# SoftCore_SA_P3.net
KiCad netlist of a schematic drawn in Altium Designer
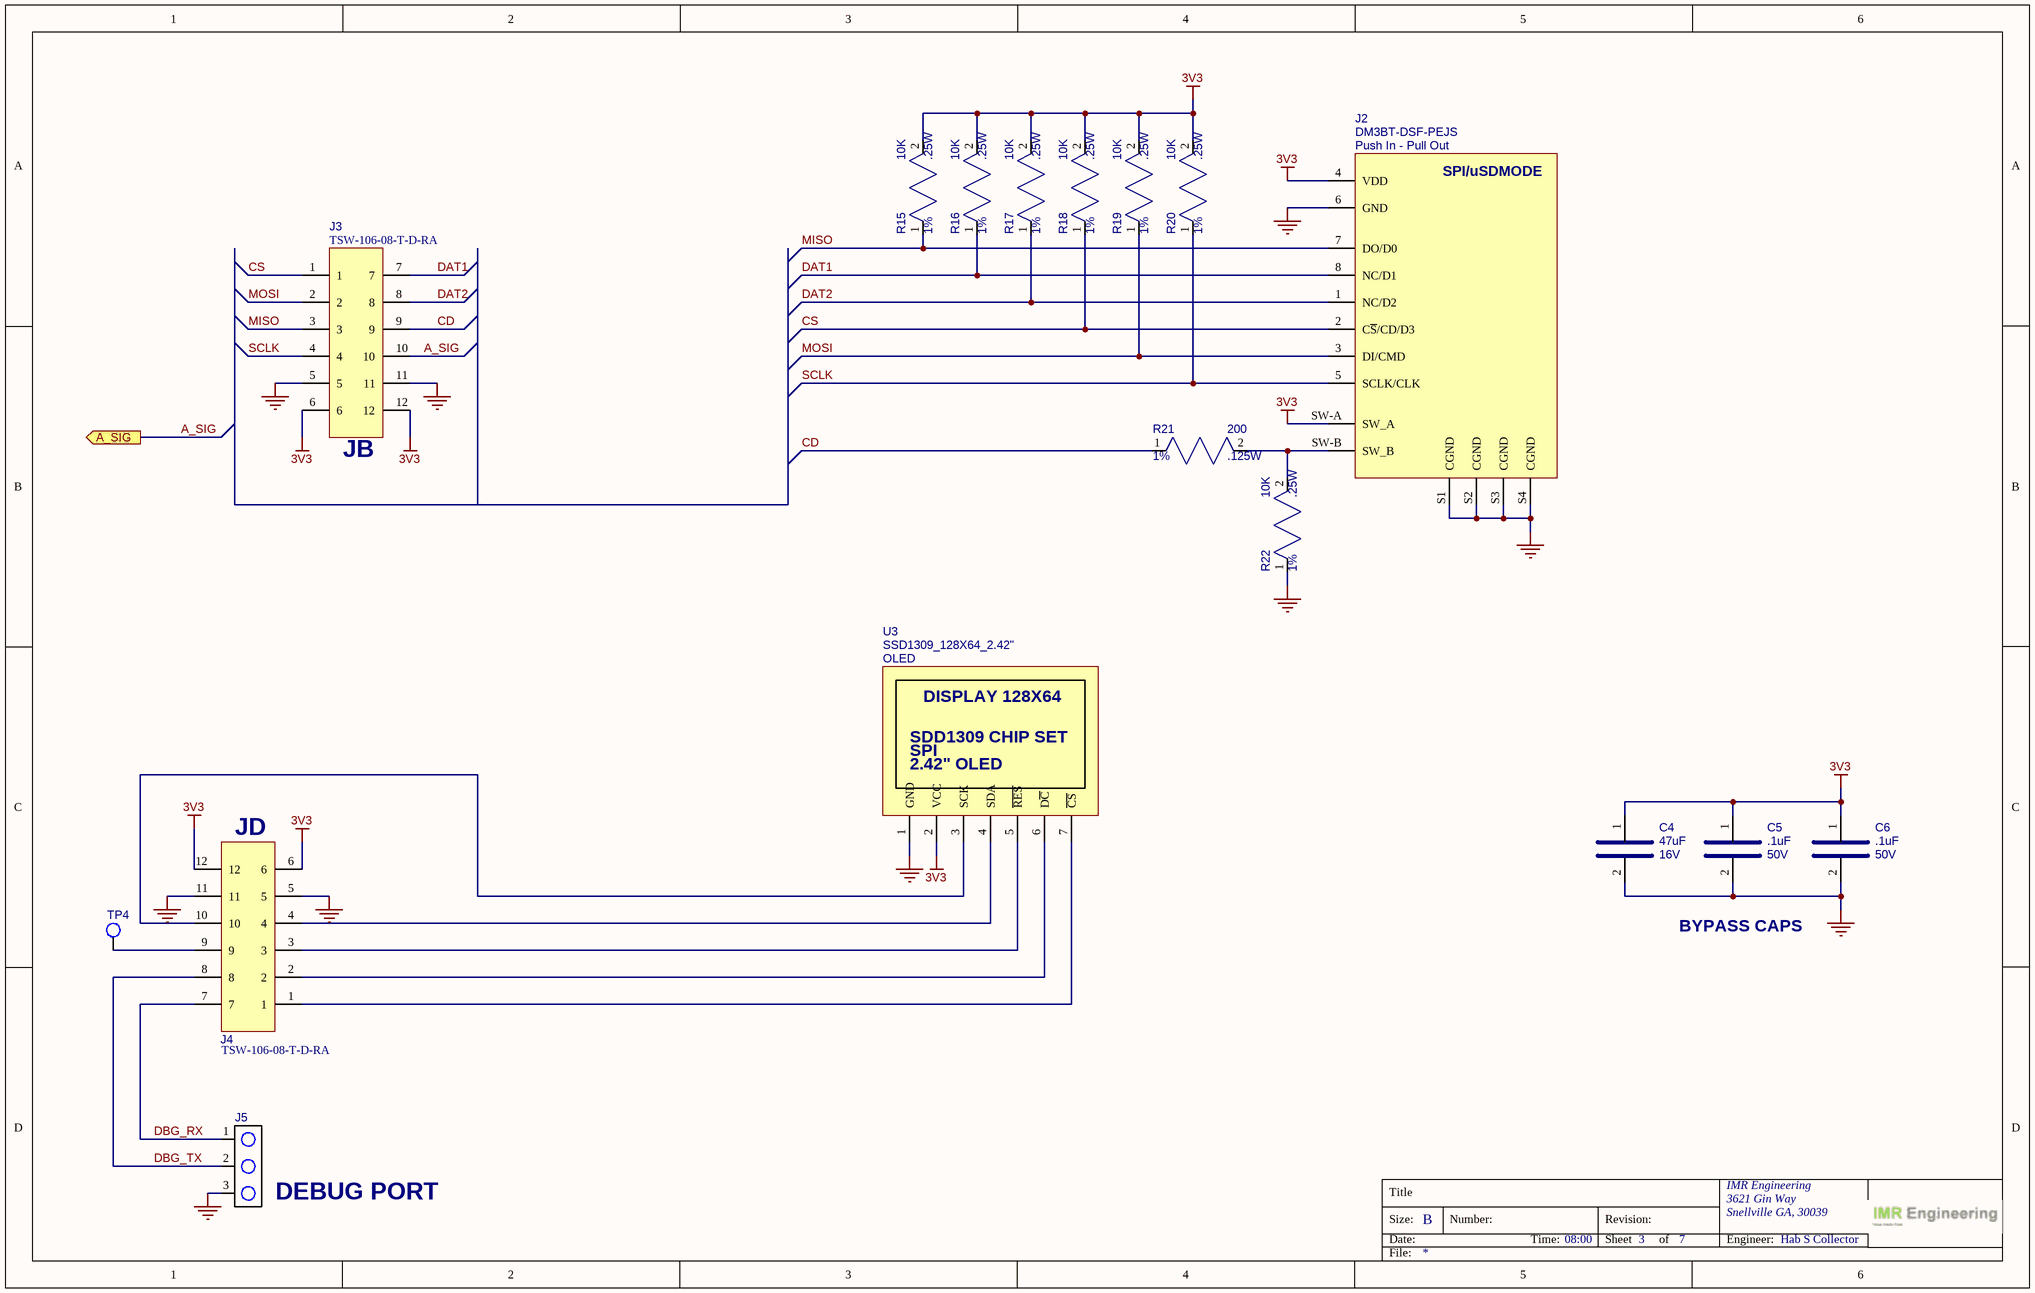
[diagram p0: SoftCore_SA_P3.SchDoc]

(export (version "E")
  (design (tool "Eeschema 10.0.6"))
  (components
    (comp (ref "C4")
      (value "47uF")
      (footprint "CAP_1210")
      (description "CAP CER 47UF 50V X5R 1210")
      (fields
        (field (name "MFG") "Murata Electronics")
        (field (name "VOLTAGE") "16V")
        (field (name "Comment") "GRM32ER60J476ME20L")
      )
      (libsource (lib "IMR_LIB_SCH_R2") (part "CAP_SMD_47UF_16V_1210"))
    )
    (comp (ref "C5")
      (value ".1uF")
      (footprint "CAP_0805")
      (description "CAP CER 0.1UF 50V X7R 0805")
      (fields
        (field (name "MFG") "KYOCERA AVX")
        (field (name "VOLTAGE") "50V")
        (field (name "Comment") "KGM21NR71H104KT")
      )
      (libsource (lib "IMR_LIB_SCH_R2") (part "CAP_SMD_0.1UF_50V_0805"))
    )
    (comp (ref "C6")
      (value ".1uF")
      (footprint "CAP_0805")
      (description "CAP CER 0.1UF 50V X7R 0805")
      (fields
        (field (name "MFG") "KYOCERA AVX")
        (field (name "VOLTAGE") "50V")
        (field (name "Comment") "KGM21NR71H104KT")
      )
      (libsource (lib "IMR_LIB_SCH_R2") (part "CAP_SMD_0.1UF_50V_0805"))
    )
    (comp (ref "J2")
      (value "Push In - Pull Out")
      (footprint "HRS_DM3BT-DSF-PEJS")
      (description "CONN MICRO SD CARD R/A SMD")
      (fields
        (field (name "MFG") "Hirose Electric Co Ltd")
        (field (name "MFG_PN") "DM3BT-DSF-PEJS")
        (field (name "Comment") "DM3BT-DSF-PEJS")
      )
      (libsource (lib "IMR_LIB_SCH_R2") (part "CONN_MICRO-SD_DM3BT-DSF-PEJS"))
    )
    (comp (ref "J3")
      (value "TSW-106-08-T-D-RA")
      (footprint "SAMTEC_TSW-106-08-T-D-RA")
      (description "CONN HEADER R/A 12POS 2.54MM")
      (fields (field (name "MFG") "Samtec Inc.") (field (name "MFG_PN") "TSW-106-08-T-D-RA"))
      (libsource (lib "") (part "CONN_HEADER_12P_100MIL_RA_1"))
    )
    (comp (ref "J4")
      (value "TSW-106-08-T-D-RA")
      (footprint "SAMTEC_TSW-106-08-T-D-RA")
      (description "CONN HEADER R/A 12POS 2.54MM")
      (fields (field (name "MFG") "Samtec Inc.") (field (name "MFG_PN") "TSW-106-08-T-D-RA"))
      (libsource (lib "IMR_LIB_SCH_R2") (part "CONN_HEADER_12P_100MIL_RA"))
    )
    (comp (ref "J5")
      (value "PREC003SFAN-RC")
      (footprint "HDR_1X3_100MILL")
      (description "CONN HEADER VERT 3POS 2.54MM")
      (fields (field (name "MFG") "Sullins Connector Solutions"))
      (libsource (lib "IMR_LIB_SCH_R2") (part "CONN_HEADER_3P_100MIL_VERT"))
    )
    (comp (ref "R15")
      (value "10K")
      (footprint "RES_0805")
      (description "RES SMD 10K OHM 1% 1/4W 0805")
      (fields
        (field (name "MFG") "Yageo")
        (field (name "POWER") ".25W")
        (field (name "TOLERANCE") "1%")
        (field (name "Comment") "RC0805FR-7W10KL")
      )
      (libsource (lib "IMR_LIB_SCH_R2") (part "RES_SMD_10K_0805_1/4W_1%"))
    )
    (comp (ref "R16")
      (value "10K")
      (footprint "RES_0805")
      (description "RES SMD 10K OHM 1% 1/4W 0805")
      (fields
        (field (name "MFG") "Yageo")
        (field (name "POWER") ".25W")
        (field (name "TOLERANCE") "1%")
        (field (name "Comment") "RC0805FR-7W10KL")
      )
      (libsource (lib "IMR_LIB_SCH_R2") (part "RES_SMD_10K_0805_1/4W_1%"))
    )
    (comp (ref "R17")
      (value "10K")
      (footprint "RES_0805")
      (description "RES SMD 10K OHM 1% 1/4W 0805")
      (fields
        (field (name "MFG") "Yageo")
        (field (name "POWER") ".25W")
        (field (name "TOLERANCE") "1%")
        (field (name "Comment") "RC0805FR-7W10KL")
      )
      (libsource (lib "IMR_LIB_SCH_R2") (part "RES_SMD_10K_0805_1/4W_1%"))
    )
    (comp (ref "R18")
      (value "10K")
      (footprint "RES_0805")
      (description "RES SMD 10K OHM 1% 1/4W 0805")
      (fields
        (field (name "MFG") "Yageo")
        (field (name "POWER") ".25W")
        (field (name "TOLERANCE") "1%")
        (field (name "Comment") "RC0805FR-7W10KL")
      )
      (libsource (lib "IMR_LIB_SCH_R2") (part "RES_SMD_10K_0805_1/4W_1%"))
    )
    (comp (ref "R19")
      (value "10K")
      (footprint "RES_0805")
      (description "RES SMD 10K OHM 1% 1/4W 0805")
      (fields
        (field (name "MFG") "Yageo")
        (field (name "POWER") ".25W")
        (field (name "TOLERANCE") "1%")
        (field (name "Comment") "RC0805FR-7W10KL")
      )
      (libsource (lib "IMR_LIB_SCH_R2") (part "RES_SMD_10K_0805_1/4W_1%"))
    )
    (comp (ref "R20")
      (value "10K")
      (footprint "RES_0805")
      (description "RES SMD 10K OHM 1% 1/4W 0805")
      (fields
        (field (name "MFG") "Yageo")
        (field (name "POWER") ".25W")
        (field (name "TOLERANCE") "1%")
        (field (name "Comment") "RC0805FR-7W10KL")
      )
      (libsource (lib "IMR_LIB_SCH_R2") (part "RES_SMD_10K_0805_1/4W_1%"))
    )
    (comp (ref "R21")
      (value "200")
      (footprint "RES_0805")
      (description "RES SMD 200 OHM 1% 1/8W 0805")
      (fields
        (field (name "MFG") "Yageo")
        (field (name "POWER") ".125W")
        (field (name "TOLERANCE") "1%")
        (field (name "Comment") "RC0805FR-07200RL")
      )
      (libsource (lib "IMR_LIB_SCH_R2") (part "RES_SMD_200_0805_1/8W_1%"))
    )
    (comp (ref "R22")
      (value "10K")
      (footprint "RES_0805")
      (description "RES SMD 10K OHM 1% 1/4W 0805")
      (fields
        (field (name "MFG") "Yageo")
        (field (name "POWER") ".25W")
        (field (name "TOLERANCE") "1%")
        (field (name "Comment") "RC0805FR-7W10KL")
      )
      (libsource (lib "IMR_LIB_SCH_R2") (part "RES_SMD_10K_0805_1/4W_1%"))
    )
    (comp (ref "TP4")
      (value "~")
      (footprint "TEST_POINT_20MIL_TH")
      (description "TEST POINT TH 20MIL HOLE")
      (libsource (lib "IMR_LIB_SCH_R2") (part "CONN_TEST_POINT_TH_PAD_20MIL"))
    )
    (comp (ref "U3")
      (value "SSD1309_128X64_2.42\"")
      (footprint "MODULE_DISPLAY_128X64_2.42")
      (description "DISPLAY 128X64 SSD1309 2.42\" OLED WHITE")
      (fields
        (field (name "MFG") "UNKNOWN")
        (field (name "TYPE") "OLED")
        (field (name "MFG_PN") "SSD1309_128X64_2.42\"")
      )
      (libsource (lib "IMR_LIB_SCH_R2") (part "MODULE_DISPLAY_128X64_2.42"))
    )
  )
  (nets
    (net (code "1") (name "/A_SIG") (class "Default")
      (node (ref "J3") (pin "10") (pinfunction "10_10") (pintype "passive"))
    )
    (net (code "2") (name "/CD") (class "Default")
      (node (ref "J3") (pin "9") (pinfunction "9_9") (pintype "passive"))
      (node (ref "R21") (pin "1") (pinfunction "1_1") (pintype "passive"))
    )
    (net (code "3") (name "/CS") (class "Default")
      (node (ref "J2") (pin "2") (pinfunction "C~{S}/CD/D3_2") (pintype "passive"))
      (node (ref "J3") (pin "1") (pinfunction "1_1") (pintype "passive"))
      (node (ref "R18") (pin "1") (pinfunction "1_1") (pintype "passive"))
    )
    (net (code "4") (name "/DAT1") (class "Default")
      (node (ref "J2") (pin "8") (pinfunction "NC/D1_8") (pintype "passive"))
      (node (ref "J3") (pin "7") (pinfunction "7_7") (pintype "passive"))
      (node (ref "R16") (pin "1") (pinfunction "1_1") (pintype "passive"))
    )
    (net (code "5") (name "/DAT2") (class "Default")
      (node (ref "J2") (pin "1") (pinfunction "NC/D2_1") (pintype "passive"))
      (node (ref "J3") (pin "8") (pinfunction "8_8") (pintype "passive"))
      (node (ref "R17") (pin "1") (pinfunction "1_1") (pintype "passive"))
    )
    (net (code "6") (name "/DBG_RX") (class "Default")
      (node (ref "J4") (pin "7") (pinfunction "7_7") (pintype "passive"))
      (node (ref "J5") (pin "1") (pintype "passive"))
    )
    (net (code "7") (name "/DBG_TX") (class "Default")
      (node (ref "J4") (pin "8") (pinfunction "8_8") (pintype "passive"))
      (node (ref "J5") (pin "2") (pintype "passive"))
    )
    (net (code "8") (name "/MISO") (class "Default")
      (node (ref "J2") (pin "7") (pinfunction "DO/D0_7") (pintype "passive"))
      (node (ref "J3") (pin "3") (pinfunction "3_3") (pintype "passive"))
      (node (ref "R15") (pin "1") (pinfunction "1_1") (pintype "passive"))
    )
    (net (code "9") (name "/MOSI") (class "Default")
      (node (ref "J2") (pin "3") (pinfunction "DI/CMD_3") (pintype "passive"))
      (node (ref "J3") (pin "2") (pinfunction "2_2") (pintype "passive"))
      (node (ref "R19") (pin "1") (pinfunction "1_1") (pintype "passive"))
    )
    (net (code "10") (name "/SCLK") (class "Default")
      (node (ref "J2") (pin "5") (pinfunction "SCLK/CLK_5") (pintype "passive"))
      (node (ref "J3") (pin "4") (pinfunction "4_4") (pintype "passive"))
      (node (ref "R20") (pin "1") (pinfunction "1_1") (pintype "passive"))
    )
    (net (code "11") (name "3V3") (class "Default")
      (node (ref "C4") (pin "1") (pinfunction "1_1") (pintype "passive"))
      (node (ref "C5") (pin "1") (pinfunction "1_1") (pintype "passive"))
      (node (ref "C6") (pin "1") (pinfunction "1_1") (pintype "passive"))
      (node (ref "J2") (pin "4") (pinfunction "VDD_4") (pintype "passive"))
      (node (ref "J2") (pin "SW-A") (pinfunction "SW_A_SW-A") (pintype "passive"))
      (node (ref "J3") (pin "12") (pinfunction "12_12") (pintype "passive"))
      (node (ref "J3") (pin "6") (pinfunction "6_6") (pintype "passive"))
      (node (ref "J4") (pin "12") (pinfunction "12_12") (pintype "passive"))
      (node (ref "J4") (pin "6") (pinfunction "6_6") (pintype "passive"))
      (node (ref "R15") (pin "2") (pinfunction "2_2") (pintype "passive"))
      (node (ref "R16") (pin "2") (pinfunction "2_2") (pintype "passive"))
      (node (ref "R17") (pin "2") (pinfunction "2_2") (pintype "passive"))
      (node (ref "R18") (pin "2") (pinfunction "2_2") (pintype "passive"))
      (node (ref "R19") (pin "2") (pinfunction "2_2") (pintype "passive"))
      (node (ref "R20") (pin "2") (pinfunction "2_2") (pintype "passive"))
      (node (ref "U3") (pin "2") (pinfunction "VCC_2") (pintype "passive"))
    )
    (net (code "12") (name "GND") (class "Default")
      (node (ref "C4") (pin "2") (pinfunction "2_2") (pintype "passive"))
      (node (ref "C5") (pin "2") (pinfunction "2_2") (pintype "passive"))
      (node (ref "C6") (pin "2") (pinfunction "2_2") (pintype "passive"))
      (node (ref "J2") (pin "6") (pinfunction "GND_6") (pintype "passive"))
      (node (ref "J2") (pin "S1") (pinfunction "CGND_S1") (pintype "passive"))
      (node (ref "J2") (pin "S2") (pinfunction "CGND_S2") (pintype "passive"))
      (node (ref "J2") (pin "S3") (pinfunction "CGND_S3") (pintype "passive"))
      (node (ref "J2") (pin "S4") (pinfunction "CGND_S4") (pintype "passive"))
      (node (ref "J3") (pin "11") (pinfunction "11_11") (pintype "passive"))
      (node (ref "J3") (pin "5") (pinfunction "5_5") (pintype "passive"))
      (node (ref "J4") (pin "11") (pinfunction "11_11") (pintype "passive"))
      (node (ref "J4") (pin "5") (pinfunction "5_5") (pintype "passive"))
      (node (ref "J5") (pin "3") (pintype "passive"))
      (node (ref "R22") (pin "1") (pinfunction "1_1") (pintype "passive"))
      (node (ref "U3") (pin "1") (pinfunction "GND_1") (pintype "passive"))
    )
    (net (code "13") (name "Net-(J2-SW_B)") (class "Default")
      (node (ref "J2") (pin "SW-B") (pinfunction "SW_B_SW-B") (pintype "passive"))
      (node (ref "R21") (pin "2") (pinfunction "2_2") (pintype "passive"))
      (node (ref "R22") (pin "2") (pinfunction "2_2") (pintype "passive"))
    )
    (net (code "14") (name "Net-(J4-Pad9)") (class "Default")
      (node (ref "J4") (pin "9") (pinfunction "9_9") (pintype "passive"))
      (node (ref "TP4") (pin "1") (pintype "passive"))
    )
    (net (code "15") (name "Net-(U3-D~{C})") (class "Default")
      (node (ref "J4") (pin "2") (pinfunction "2_2") (pintype "passive"))
      (node (ref "U3") (pin "6") (pinfunction "D~{C}_6") (pintype "passive"))
    )
    (net (code "16") (name "Net-(U3-SCK)") (class "Default")
      (node (ref "J4") (pin "10") (pinfunction "10_10") (pintype "passive"))
      (node (ref "U3") (pin "3") (pinfunction "SCK_3") (pintype "passive"))
    )
    (net (code "17") (name "Net-(U3-SDA)") (class "Default")
      (node (ref "J4") (pin "4") (pinfunction "4_4") (pintype "passive"))
      (node (ref "U3") (pin "4") (pinfunction "SDA_4") (pintype "passive"))
    )
    (net (code "18") (name "Net-(U3-~{CS})") (class "Default")
      (node (ref "J4") (pin "1") (pinfunction "1_1") (pintype "passive"))
      (node (ref "U3") (pin "7") (pinfunction "~{CS}_7") (pintype "passive"))
    )
    (net (code "19") (name "Net-(U3-~{RES})") (class "Default")
      (node (ref "J4") (pin "3") (pinfunction "3_3") (pintype "passive"))
      (node (ref "U3") (pin "5") (pinfunction "~{RES}_5") (pintype "passive"))
    )
  )
)
